# CATS-EUROC-MCU.net
KiCad netlist of a schematic drawn in Altium Designer
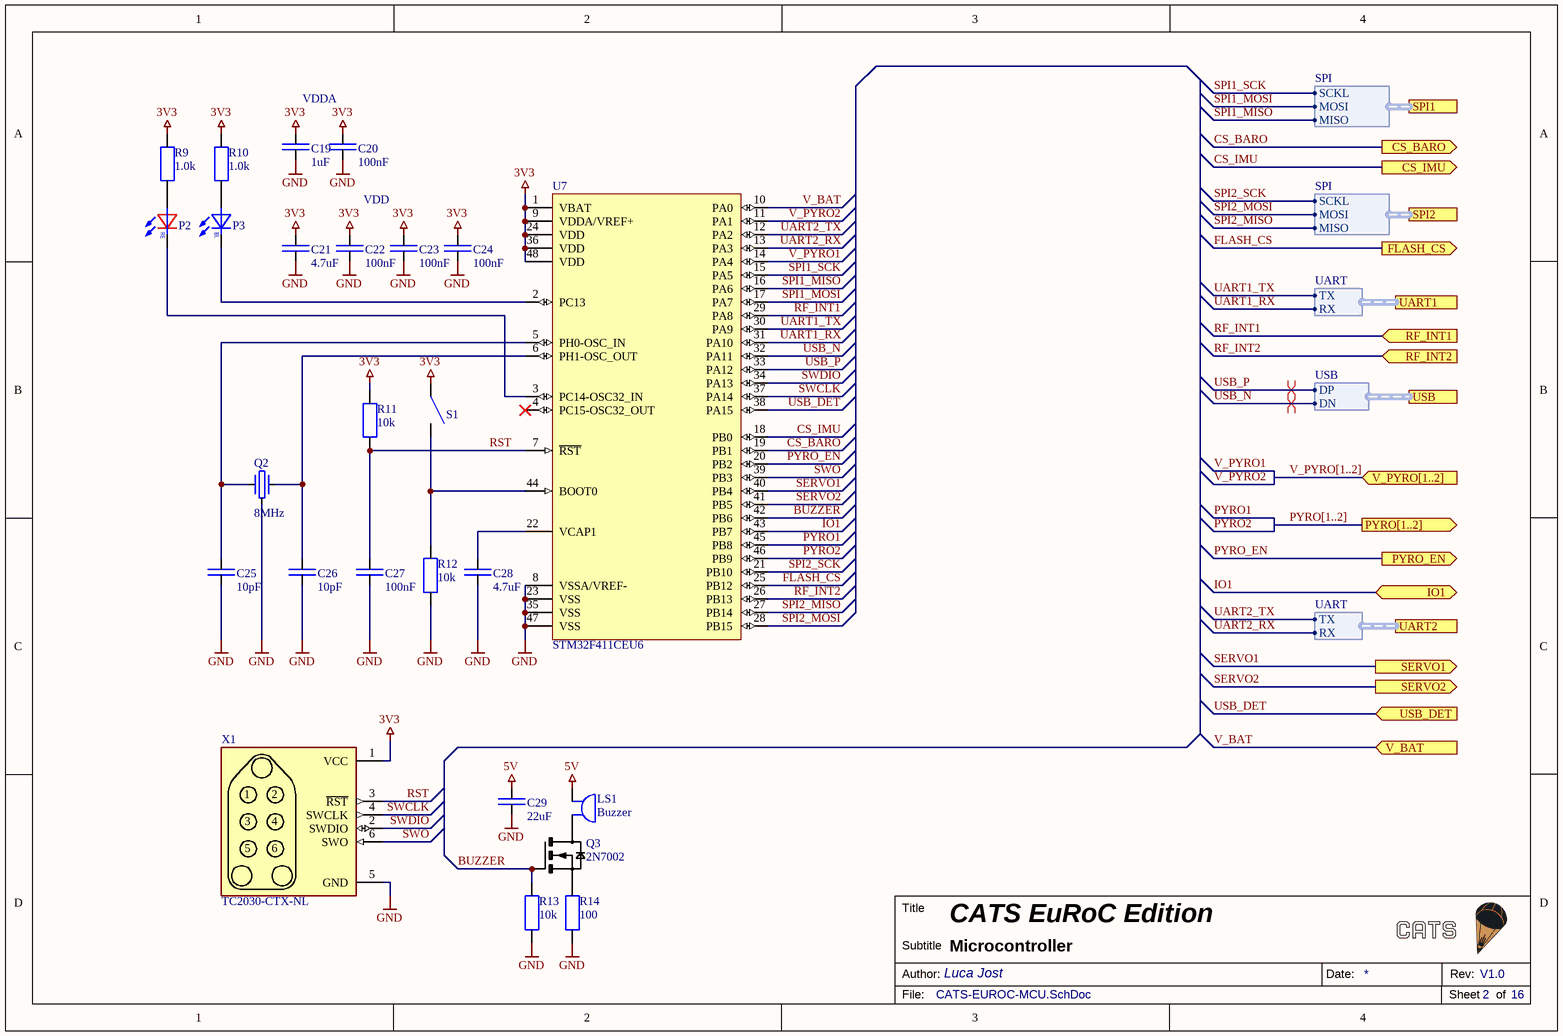
[diagram p0: CATS-EUROC-MCU.SchDoc]

(export (version "E")
  (design (tool "Eeschema 10.0.6"))
  (components
    (comp (ref "C19")
      (value "1uF")
      (footprint "SMD Keramikkondensator 0402")
      (description "SMD Ceramic Capacitor E6")
      (libsource (lib "CATS-EUROC") (part "E6 - 1uF"))
    )
    (comp (ref "C20")
      (value "100nF")
      (footprint "SMD Keramikkondensator 0402")
      (description "SMD Ceramic Capacitor E6")
      (libsource (lib "CATS-EUROC") (part "E6 - 100nF"))
    )
    (comp (ref "C21")
      (value "4.7uF")
      (footprint "SMD Keramikkondensator 0402")
      (description "SMD Ceramic Capacitor E6")
      (libsource (lib "CATS-EUROC") (part "E6 - 4.7uF"))
    )
    (comp (ref "C22")
      (value "100nF")
      (footprint "SMD Keramikkondensator 0402")
      (description "SMD Ceramic Capacitor E6")
      (libsource (lib "CATS-EUROC") (part "E6 - 100nF"))
    )
    (comp (ref "C23")
      (value "100nF")
      (footprint "SMD Keramikkondensator 0402")
      (description "SMD Ceramic Capacitor E6")
      (libsource (lib "CATS-EUROC") (part "E6 - 100nF"))
    )
    (comp (ref "C24")
      (value "100nF")
      (footprint "SMD Keramikkondensator 0402")
      (description "SMD Ceramic Capacitor E6")
      (libsource (lib "CATS-EUROC") (part "E6 - 100nF"))
    )
    (comp (ref "C25")
      (value "10pF")
      (footprint "SMD Keramikkondensator 0402")
      (description "SMD Ceramic Capacitor E6")
      (libsource (lib "CATS-EUROC") (part "E6 - 10pF"))
    )
    (comp (ref "C26")
      (value "10pF")
      (footprint "SMD Keramikkondensator 0402")
      (description "SMD Ceramic Capacitor E6")
      (libsource (lib "CATS-EUROC") (part "E6 - 10pF"))
    )
    (comp (ref "C27")
      (value "100nF")
      (footprint "SMD Keramikkondensator 0402")
      (description "SMD Ceramic Capacitor E6")
      (libsource (lib "CATS-EUROC") (part "E6 - 100nF"))
    )
    (comp (ref "C28")
      (value "4.7uF")
      (footprint "SMD Keramikkondensator 0402")
      (description "SMD Ceramic Capacitor E6")
      (libsource (lib "CATS-EUROC") (part "E6 - 4.7uF"))
    )
    (comp (ref "C29")
      (value "22uF")
      (footprint "SMD Keramikkondensator 0805")
      (description "SMD Ceramic Capacitor E6")
      (libsource (lib "CATS-EUROC") (part "E6 - 22uF"))
    )
    (comp (ref "LS1")
      (value "Buzzer")
      (footprint "SMD BUZZER CMT-8504")
      (description "Buzzers Indicator, Internally Driven Piezo 12V 10mA 3kHz 100dB @ 12V, 10cm Through Hole PC Pins")
      (libsource (lib "Other") (part "Buzzer"))
    )
    (comp (ref "P2")
      (value "LED")
      (footprint "SMD LED 0603")
      (description "Color LED")
      (libsource (lib "Diodes") (part "LED"))
    )
    (comp (ref "P3")
      (value "LED")
      (footprint "SMD LED 0603")
      (description "Color LED")
      (libsource (lib "") (part "LED_1"))
    )
    (comp (ref "Q2")
      (value "8MHz")
      (footprint "SMD Crystal 3.2X2.5X0.8")
      (description "SMD Crystal Resonators 8MHz ±10ppm SMD,3.2x2.5mm")
      (libsource (lib "Other") (part "Crystal"))
    )
    (comp (ref "Q3")
      (value "2N7002")
      (footprint "SMD MOSFET SOT-23")
      (description "MOSFET N-Channel 20V / 115mA")
      (libsource (lib "Electronic Switches") (part "2N7002"))
    )
    (comp (ref "R9")
      (value "1.0k")
      (footprint "SMD Widerstand 0402")
      (description "SMD Chip Resistor E24")
      (libsource (lib "CATS-EUROC") (part "E24 - 1.0k"))
    )
    (comp (ref "R10")
      (value "1.0k")
      (footprint "SMD Widerstand 0402")
      (description "SMD Chip Resistor E24")
      (libsource (lib "CATS-EUROC") (part "E24 - 1.0k"))
    )
    (comp (ref "R11")
      (value "10k")
      (footprint "SMD Widerstand 0402")
      (description "SMD Chip Resistor E24")
      (libsource (lib "") (part "E24 - 10k_1"))
    )
    (comp (ref "R12")
      (value "10k")
      (footprint "SMD Widerstand 0402")
      (description "SMD Chip Resistor E24")
      (libsource (lib "") (part "E24 - 10k_1"))
    )
    (comp (ref "R13")
      (value "10k")
      (footprint "SMD Widerstand 0402")
      (description "SMD Chip Resistor E24")
      (libsource (lib "CATS-EUROC") (part "E24 - 10k"))
    )
    (comp (ref "R14")
      (value "100")
      (footprint "SMD Widerstand 0805")
      (description "SMD Chip Resistor E24")
      (libsource (lib "CATS-EUROC") (part "E24 - 100"))
    )
    (comp (ref "S1")
      (value "SMD-Button")
      (footprint "SMD Button 2.5x3x1.2")
      (description "Button SPST")
      (libsource (lib "CATS-EUROC") (part "Button 3mmx2.5mm"))
    )
    (comp (ref "U7")
      (value "STM32F411CEU6")
      (footprint "SMD IC QFN-48")
      (description "ARM® Cortex®-M4 series Microcontroller IC 32-Bit 100MHz 512KB (512K x 8) FLASH 48-UFQFPN (7x7)")
      (libsource (lib "Microcontrollers") (part "STM32F411CEU6"))
    )
    (comp (ref "X1")
      (value "TC2030-CTX-NL")
      (footprint "SMD Connector TC2030")
      (description "Tag-Connect for ARM-Cortex (6-Pin)")
      (libsource (lib "Connectors") (part "TC2030-CTX-NL"))
    )
  )
  (nets
    (net (code "4") (name "/BUZZER") (class "Default")
      (node (ref "Q3") (pin "G") (pinfunction "G_G") (pintype "passive"))
      (node (ref "R13") (pin "2") (pinfunction "2_2") (pintype "passive"))
      (node (ref "U7") (pin "42") (pinfunction "PB6_42") (pintype "bidirectional"))
    )
    (net (code "5") (name "/CS_BARO") (class "Default")
      (node (ref "U7") (pin "19") (pinfunction "PB1_19") (pintype "bidirectional"))
    )
    (net (code "6") (name "/CS_IMU") (class "Default")
      (node (ref "U7") (pin "18") (pinfunction "PB0_18") (pintype "bidirectional"))
    )
    (net (code "7") (name "/FLASH_CS") (class "Default")
      (node (ref "U7") (pin "25") (pinfunction "PB12_25") (pintype "bidirectional"))
    )
    (net (code "8") (name "/IO1") (class "Default")
      (node (ref "U7") (pin "43") (pinfunction "PB7_43") (pintype "bidirectional"))
    )
    (net (code "9") (name "/PYRO1") (class "Default")
      (node (ref "U7") (pin "45") (pinfunction "PB8_45") (pintype "bidirectional"))
    )
    (net (code "10") (name "/PYRO2") (class "Default")
      (node (ref "U7") (pin "46") (pinfunction "PB9_46") (pintype "bidirectional"))
    )
    (net (code "12") (name "/PYRO_EN") (class "Default")
      (node (ref "U7") (pin "20") (pinfunction "PB2_20") (pintype "bidirectional"))
    )
    (net (code "13") (name "/RF_INT1") (class "Default")
      (node (ref "U7") (pin "29") (pinfunction "PA8_29") (pintype "bidirectional"))
    )
    (net (code "14") (name "/RF_INT2") (class "Default")
      (node (ref "U7") (pin "26") (pinfunction "PB13_26") (pintype "bidirectional"))
    )
    (net (code "15") (name "/RST") (class "Default")
      (node (ref "C27") (pin "2") (pinfunction "2_2") (pintype "passive"))
      (node (ref "R11") (pin "1") (pinfunction "1_1") (pintype "passive"))
      (node (ref "U7") (pin "7") (pinfunction "~{RST}_7") (pintype "input"))
      (node (ref "X1") (pin "3") (pinfunction "~{RST}_3") (pintype "output"))
    )
    (net (code "16") (name "/SERVO1") (class "Default")
      (node (ref "U7") (pin "40") (pinfunction "PB4_40") (pintype "bidirectional"))
    )
    (net (code "17") (name "/SERVO2") (class "Default")
      (node (ref "U7") (pin "41") (pinfunction "PB5_41") (pintype "bidirectional"))
    )
    (net (code "18") (name "/SPI1_MISO") (class "Default")
      (node (ref "U7") (pin "16") (pinfunction "PA6_16") (pintype "bidirectional"))
    )
    (net (code "19") (name "/SPI1_MOSI") (class "Default")
      (node (ref "U7") (pin "17") (pinfunction "PA7_17") (pintype "bidirectional"))
    )
    (net (code "20") (name "/SPI1_SCK") (class "Default")
      (node (ref "U7") (pin "15") (pinfunction "PA5_15") (pintype "bidirectional"))
    )
    (net (code "21") (name "/SPI2_MISO") (class "Default")
      (node (ref "U7") (pin "27") (pinfunction "PB14_27") (pintype "bidirectional"))
    )
    (net (code "22") (name "/SPI2_MOSI") (class "Default")
      (node (ref "U7") (pin "28") (pinfunction "PB15_28") (pintype "bidirectional"))
    )
    (net (code "23") (name "/SPI2_SCK") (class "Default")
      (node (ref "U7") (pin "21") (pinfunction "PB10_21") (pintype "bidirectional"))
    )
    (net (code "24") (name "/SWCLK") (class "Default")
      (node (ref "U7") (pin "37") (pinfunction "PA14_37") (pintype "bidirectional"))
      (node (ref "X1") (pin "4") (pinfunction "SWCLK_4") (pintype "output"))
    )
    (net (code "25") (name "/SWDIO") (class "Default")
      (node (ref "U7") (pin "34") (pinfunction "PA13_34") (pintype "bidirectional"))
      (node (ref "X1") (pin "2") (pinfunction "SWDIO_2") (pintype "bidirectional"))
    )
    (net (code "26") (name "/SWO") (class "Default")
      (node (ref "U7") (pin "39") (pinfunction "PB3_39") (pintype "bidirectional"))
      (node (ref "X1") (pin "6") (pinfunction "SWO_6") (pintype "input"))
    )
    (net (code "27") (name "/UART1_RX") (class "Default")
      (node (ref "U7") (pin "31") (pinfunction "PA10_31") (pintype "bidirectional"))
    )
    (net (code "28") (name "/UART1_TX") (class "Default")
      (node (ref "U7") (pin "30") (pinfunction "PA9_30") (pintype "bidirectional"))
    )
    (net (code "29") (name "/UART2_RX") (class "Default")
      (node (ref "U7") (pin "13") (pinfunction "PA3_13") (pintype "bidirectional"))
    )
    (net (code "30") (name "/UART2_TX") (class "Default")
      (node (ref "U7") (pin "12") (pinfunction "PA2_12") (pintype "bidirectional"))
    )
    (net (code "31") (name "/USB_DET") (class "Default")
      (node (ref "U7") (pin "38") (pinfunction "PA15_38") (pintype "bidirectional"))
    )
    (net (code "32") (name "/USB_N") (class "Default")
      (node (ref "U7") (pin "32") (pinfunction "PA11_32") (pintype "bidirectional"))
    )
    (net (code "33") (name "/USB_P") (class "Default")
      (node (ref "U7") (pin "33") (pinfunction "PA12_33") (pintype "bidirectional"))
    )
    (net (code "34") (name "/V_BAT") (class "Default")
      (node (ref "U7") (pin "10") (pinfunction "PA0_10") (pintype "bidirectional"))
    )
    (net (code "35") (name "/V_PYRO1") (class "Default")
      (node (ref "U7") (pin "14") (pinfunction "PA4_14") (pintype "bidirectional"))
    )
    (net (code "36") (name "/V_PYRO2") (class "Default")
      (node (ref "U7") (pin "11") (pinfunction "PA1_11") (pintype "bidirectional"))
    )
    (net (code "41") (name "3V3") (class "Default")
      (node (ref "C19") (pin "2") (pinfunction "2_2") (pintype "passive"))
      (node (ref "C20") (pin "2") (pinfunction "2_2") (pintype "passive"))
      (node (ref "C21") (pin "2") (pinfunction "2_2") (pintype "passive"))
      (node (ref "C22") (pin "2") (pinfunction "2_2") (pintype "passive"))
      (node (ref "C23") (pin "2") (pinfunction "2_2") (pintype "passive"))
      (node (ref "C24") (pin "2") (pinfunction "2_2") (pintype "passive"))
      (node (ref "R10") (pin "2") (pinfunction "2_2") (pintype "passive"))
      (node (ref "R11") (pin "2") (pinfunction "2_2") (pintype "passive"))
      (node (ref "R9") (pin "2") (pinfunction "2_2") (pintype "passive"))
      (node (ref "S1") (pin "1") (pinfunction "1_1") (pintype "passive"))
      (node (ref "U7") (pin "1") (pinfunction "VBAT_1") (pintype "passive"))
      (node (ref "U7") (pin "24") (pinfunction "VDD_24") (pintype "passive"))
      (node (ref "U7") (pin "36") (pinfunction "VDD_36") (pintype "passive"))
      (node (ref "U7") (pin "48") (pinfunction "VDD_48") (pintype "passive"))
      (node (ref "U7") (pin "9") (pinfunction "VDDA/VREF+_9") (pintype "passive"))
      (node (ref "X1") (pin "1") (pinfunction "VCC_1") (pintype "power_in"))
    )
    (net (code "42") (name "5V") (class "Default")
      (node (ref "C29") (pin "2") (pinfunction "2_2") (pintype "passive"))
      (node (ref "LS1") (pin "1") (pinfunction "1_1") (pintype "passive"))
    )
    (net (code "43") (name "GND") (class "Default")
      (node (ref "C19") (pin "1") (pinfunction "1_1") (pintype "passive"))
      (node (ref "C20") (pin "1") (pinfunction "1_1") (pintype "passive"))
      (node (ref "C21") (pin "1") (pinfunction "1_1") (pintype "passive"))
      (node (ref "C22") (pin "1") (pinfunction "1_1") (pintype "passive"))
      (node (ref "C23") (pin "1") (pinfunction "1_1") (pintype "passive"))
      (node (ref "C24") (pin "1") (pinfunction "1_1") (pintype "passive"))
      (node (ref "C25") (pin "1") (pinfunction "1_1") (pintype "passive"))
      (node (ref "C26") (pin "1") (pinfunction "1_1") (pintype "passive"))
      (node (ref "C27") (pin "1") (pinfunction "1_1") (pintype "passive"))
      (node (ref "C28") (pin "1") (pinfunction "1_1") (pintype "passive"))
      (node (ref "C29") (pin "1") (pinfunction "1_1") (pintype "passive"))
      (node (ref "Q2") (pin "3") (pinfunction "3_3") (pintype "power_in"))
      (node (ref "R12") (pin "1") (pinfunction "1_1") (pintype "passive"))
      (node (ref "R13") (pin "1") (pinfunction "1_1") (pintype "passive"))
      (node (ref "R14") (pin "1") (pinfunction "1_1") (pintype "passive"))
      (node (ref "U7") (pin "23") (pinfunction "VSS_23") (pintype "passive"))
      (node (ref "U7") (pin "35") (pinfunction "VSS_35") (pintype "passive"))
      (node (ref "U7") (pin "47") (pinfunction "VSS_47") (pintype "passive"))
      (node (ref "U7") (pin "8") (pinfunction "VSSA/VREF-_8") (pintype "passive"))
      (node (ref "X1") (pin "5") (pinfunction "GND_5") (pintype "power_in"))
    )
    (net (code "44") (name "Net-(LS1-Pad2)") (class "Default")
      (node (ref "LS1") (pin "2") (pinfunction "2_2") (pintype "passive"))
      (node (ref "Q3") (pin "D") (pinfunction "D_D") (pintype "passive"))
    )
    (net (code "45") (name "Net-(P2-PadA)") (class "Default")
      (node (ref "P2") (pin "A") (pinfunction "A_A") (pintype "passive"))
      (node (ref "R9") (pin "1") (pinfunction "1_1") (pintype "passive"))
    )
    (net (code "46") (name "Net-(P3-PadA)") (class "Default")
      (node (ref "P3") (pin "A") (pinfunction "A_A") (pintype "passive"))
      (node (ref "R10") (pin "1") (pinfunction "1_1") (pintype "passive"))
    )
    (net (code "47") (name "Net-(Q3-PadS)") (class "Default")
      (node (ref "Q3") (pin "S") (pinfunction "S_S") (pintype "passive"))
      (node (ref "R14") (pin "2") (pinfunction "2_2") (pintype "passive"))
    )
    (net (code "48") (name "Net-(U7-BOOT0)") (class "Default")
      (node (ref "R12") (pin "2") (pinfunction "2_2") (pintype "passive"))
      (node (ref "S1") (pin "2") (pinfunction "2_2") (pintype "passive"))
      (node (ref "U7") (pin "44") (pinfunction "BOOT0_44") (pintype "input"))
    )
    (net (code "49") (name "Net-(U7-PC13)") (class "Default")
      (node (ref "P3") (pin "K") (pinfunction "K_K") (pintype "passive"))
      (node (ref "U7") (pin "2") (pinfunction "PC13_2") (pintype "bidirectional"))
    )
    (net (code "50") (name "Net-(U7-PC14-OSC32_IN)") (class "Default")
      (node (ref "P2") (pin "K") (pinfunction "K_K") (pintype "passive"))
      (node (ref "U7") (pin "3") (pinfunction "PC14-OSC32_IN_3") (pintype "bidirectional"))
    )
    (net (code "51") (name "Net-(U7-PH0-OSC_IN)") (class "Default")
      (node (ref "C25") (pin "2") (pinfunction "2_2") (pintype "passive"))
      (node (ref "Q2") (pin "1") (pinfunction "1_1") (pintype "passive"))
      (node (ref "U7") (pin "5") (pinfunction "PH0-OSC_IN_5") (pintype "bidirectional"))
    )
    (net (code "52") (name "Net-(U7-PH1-OSC_OUT)") (class "Default")
      (node (ref "C26") (pin "2") (pinfunction "2_2") (pintype "passive"))
      (node (ref "Q2") (pin "2") (pinfunction "2_2") (pintype "passive"))
      (node (ref "U7") (pin "6") (pinfunction "PH1-OSC_OUT_6") (pintype "bidirectional"))
    )
    (net (code "53") (name "Net-(U7-VCAP1)") (class "Default")
      (node (ref "C28") (pin "2") (pinfunction "2_2") (pintype "passive"))
      (node (ref "U7") (pin "22") (pinfunction "VCAP1_22") (pintype "passive"))
    )
    (net (code "54") (name "unconnected-(U7-PC15-OSC32_OUT-Pad4)") (class "Default")
      (node (ref "U7") (pin "4") (pinfunction "PC15-OSC32_OUT_4") (pintype "bidirectional+no_connect"))
    )
  )
)
